# iblock-breadboard.net
KiCad netlist of a schematic drawn in EAGLE
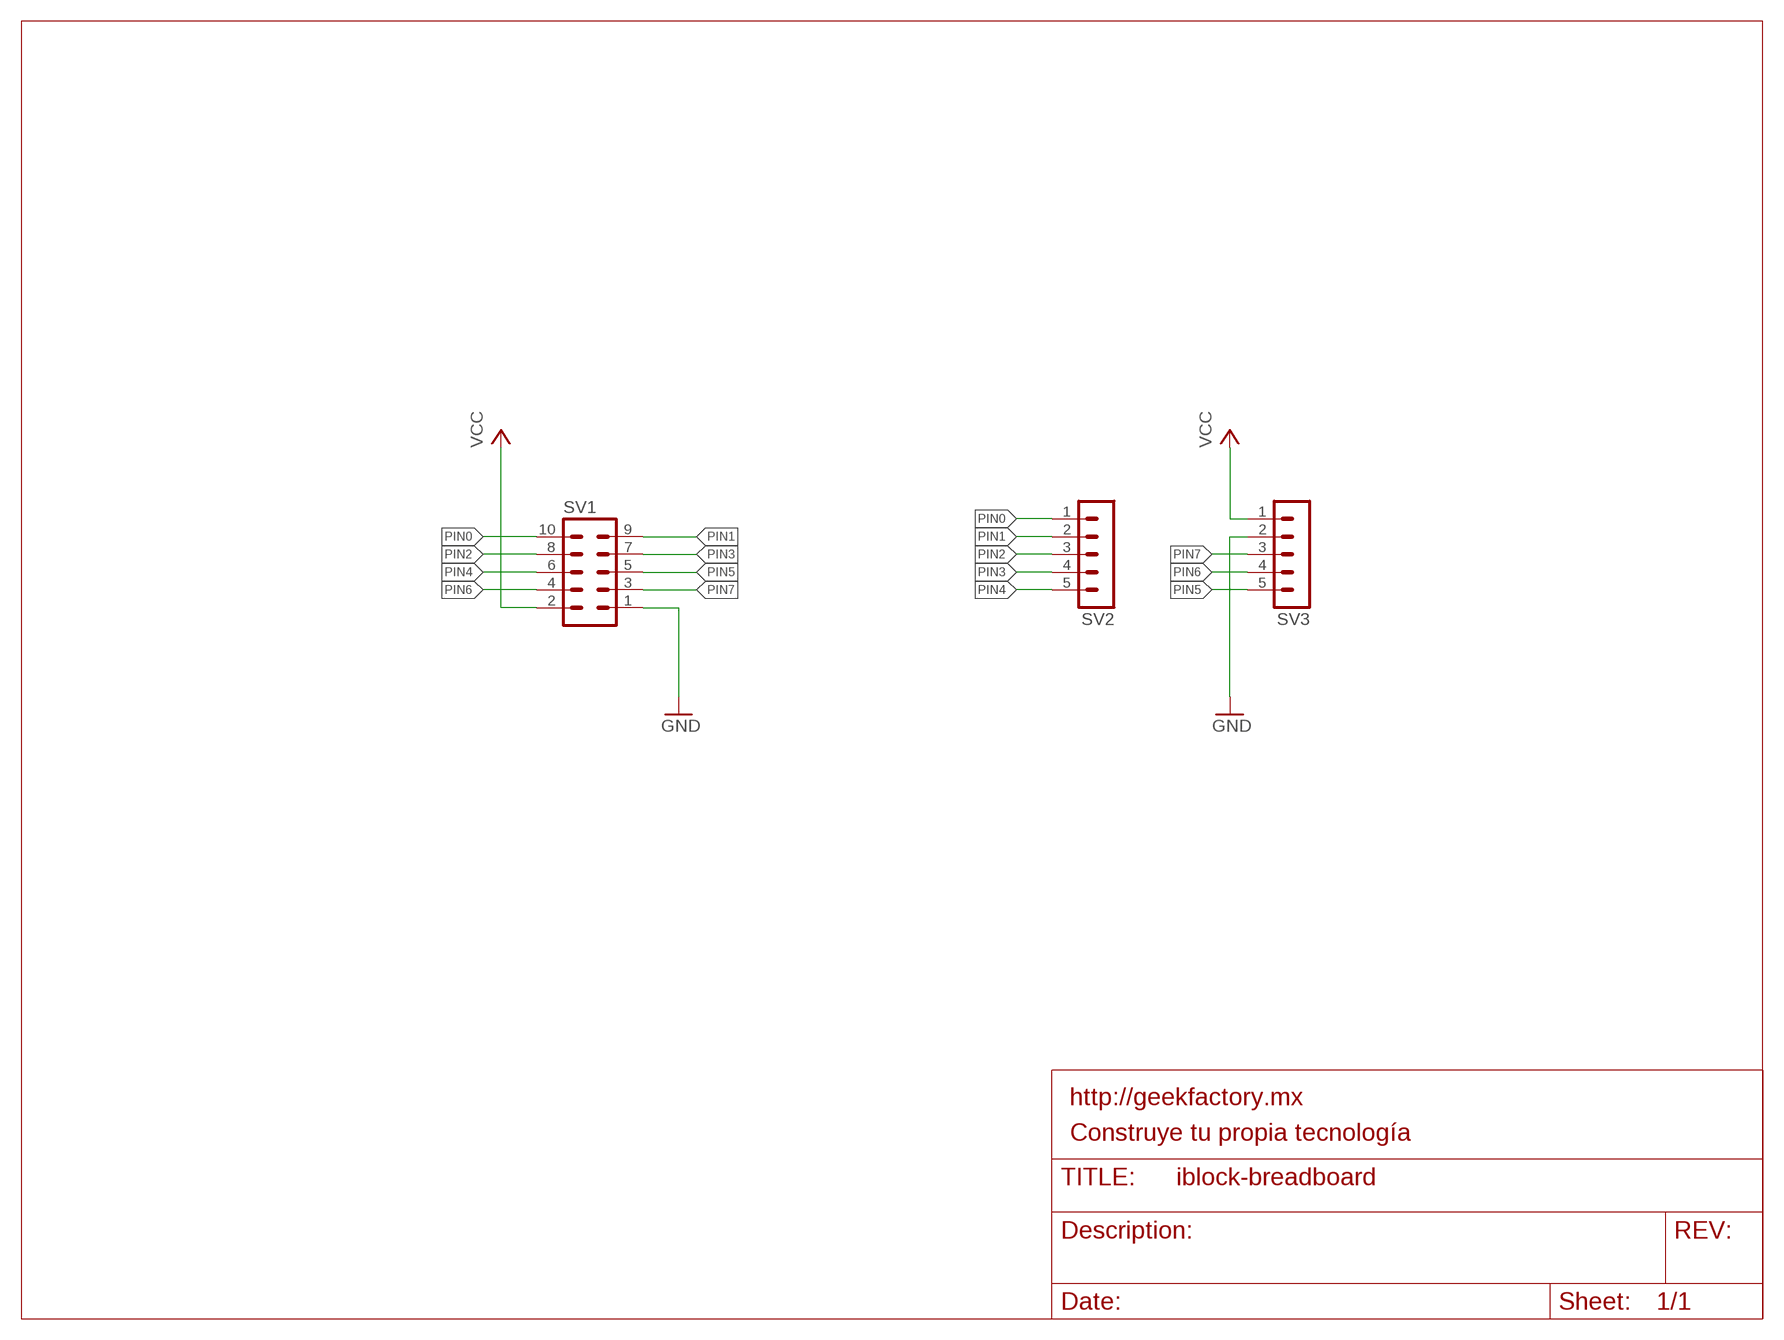
[diagram p0: schematic, sheet 1]

(export (version "E")
  (design (tool "Eeschema 10.0.6"))
  (components
    (comp (ref "SV1")
      (value "MA05-2")
      (footprint "eagle-import:MA05-2")
      (libsource (lib "eagle-import") (part "MA05-2"))
    )
    (comp (ref "SV2")
      (value "MA05-1")
      (footprint "eagle-import:MA05-1")
      (libsource (lib "eagle-import") (part "MA05-1"))
    )
    (comp (ref "SV3")
      (value "MA05-1")
      (footprint "eagle-import:MA05-1")
      (libsource (lib "eagle-import") (part "MA05-1"))
    )
  )
  (nets
    (net (code "1") (name "GND") (class "Default")
      (node (ref "SV1") (pin "1") (pinfunction "1_1") (pintype "passive"))
      (node (ref "SV3") (pin "2") (pinfunction "2_2") (pintype "passive"))
    )
    (net (code "2") (name "PIN0") (class "Default")
      (node (ref "SV1") (pin "10") (pinfunction "10_10") (pintype "passive"))
      (node (ref "SV2") (pin "1") (pinfunction "1_1") (pintype "passive"))
    )
    (net (code "3") (name "PIN1") (class "Default")
      (node (ref "SV1") (pin "9") (pinfunction "9_9") (pintype "passive"))
      (node (ref "SV2") (pin "2") (pinfunction "2_2") (pintype "passive"))
    )
    (net (code "4") (name "PIN2") (class "Default")
      (node (ref "SV1") (pin "8") (pinfunction "8_8") (pintype "passive"))
      (node (ref "SV2") (pin "3") (pinfunction "3_3") (pintype "passive"))
    )
    (net (code "5") (name "PIN3") (class "Default")
      (node (ref "SV1") (pin "7") (pinfunction "7_7") (pintype "passive"))
      (node (ref "SV2") (pin "4") (pinfunction "4_4") (pintype "passive"))
    )
    (net (code "6") (name "PIN4") (class "Default")
      (node (ref "SV1") (pin "6") (pinfunction "6_6") (pintype "passive"))
      (node (ref "SV2") (pin "5") (pinfunction "5_5") (pintype "passive"))
    )
    (net (code "7") (name "PIN5") (class "Default")
      (node (ref "SV1") (pin "5") (pinfunction "5_5") (pintype "passive"))
      (node (ref "SV3") (pin "5") (pinfunction "5_5") (pintype "passive"))
    )
    (net (code "8") (name "PIN6") (class "Default")
      (node (ref "SV1") (pin "4") (pinfunction "4_4") (pintype "passive"))
      (node (ref "SV3") (pin "4") (pinfunction "4_4") (pintype "passive"))
    )
    (net (code "9") (name "PIN7") (class "Default")
      (node (ref "SV1") (pin "3") (pinfunction "3_3") (pintype "passive"))
      (node (ref "SV3") (pin "3") (pinfunction "3_3") (pintype "passive"))
    )
    (net (code "10") (name "VCC") (class "Default")
      (node (ref "SV1") (pin "2") (pinfunction "2_2") (pintype "passive"))
      (node (ref "SV3") (pin "1") (pinfunction "1_1") (pintype "passive"))
    )
  )
)
